# Pin28_Schematic.net
KiCad netlist of a schematic drawn in Altium Designer
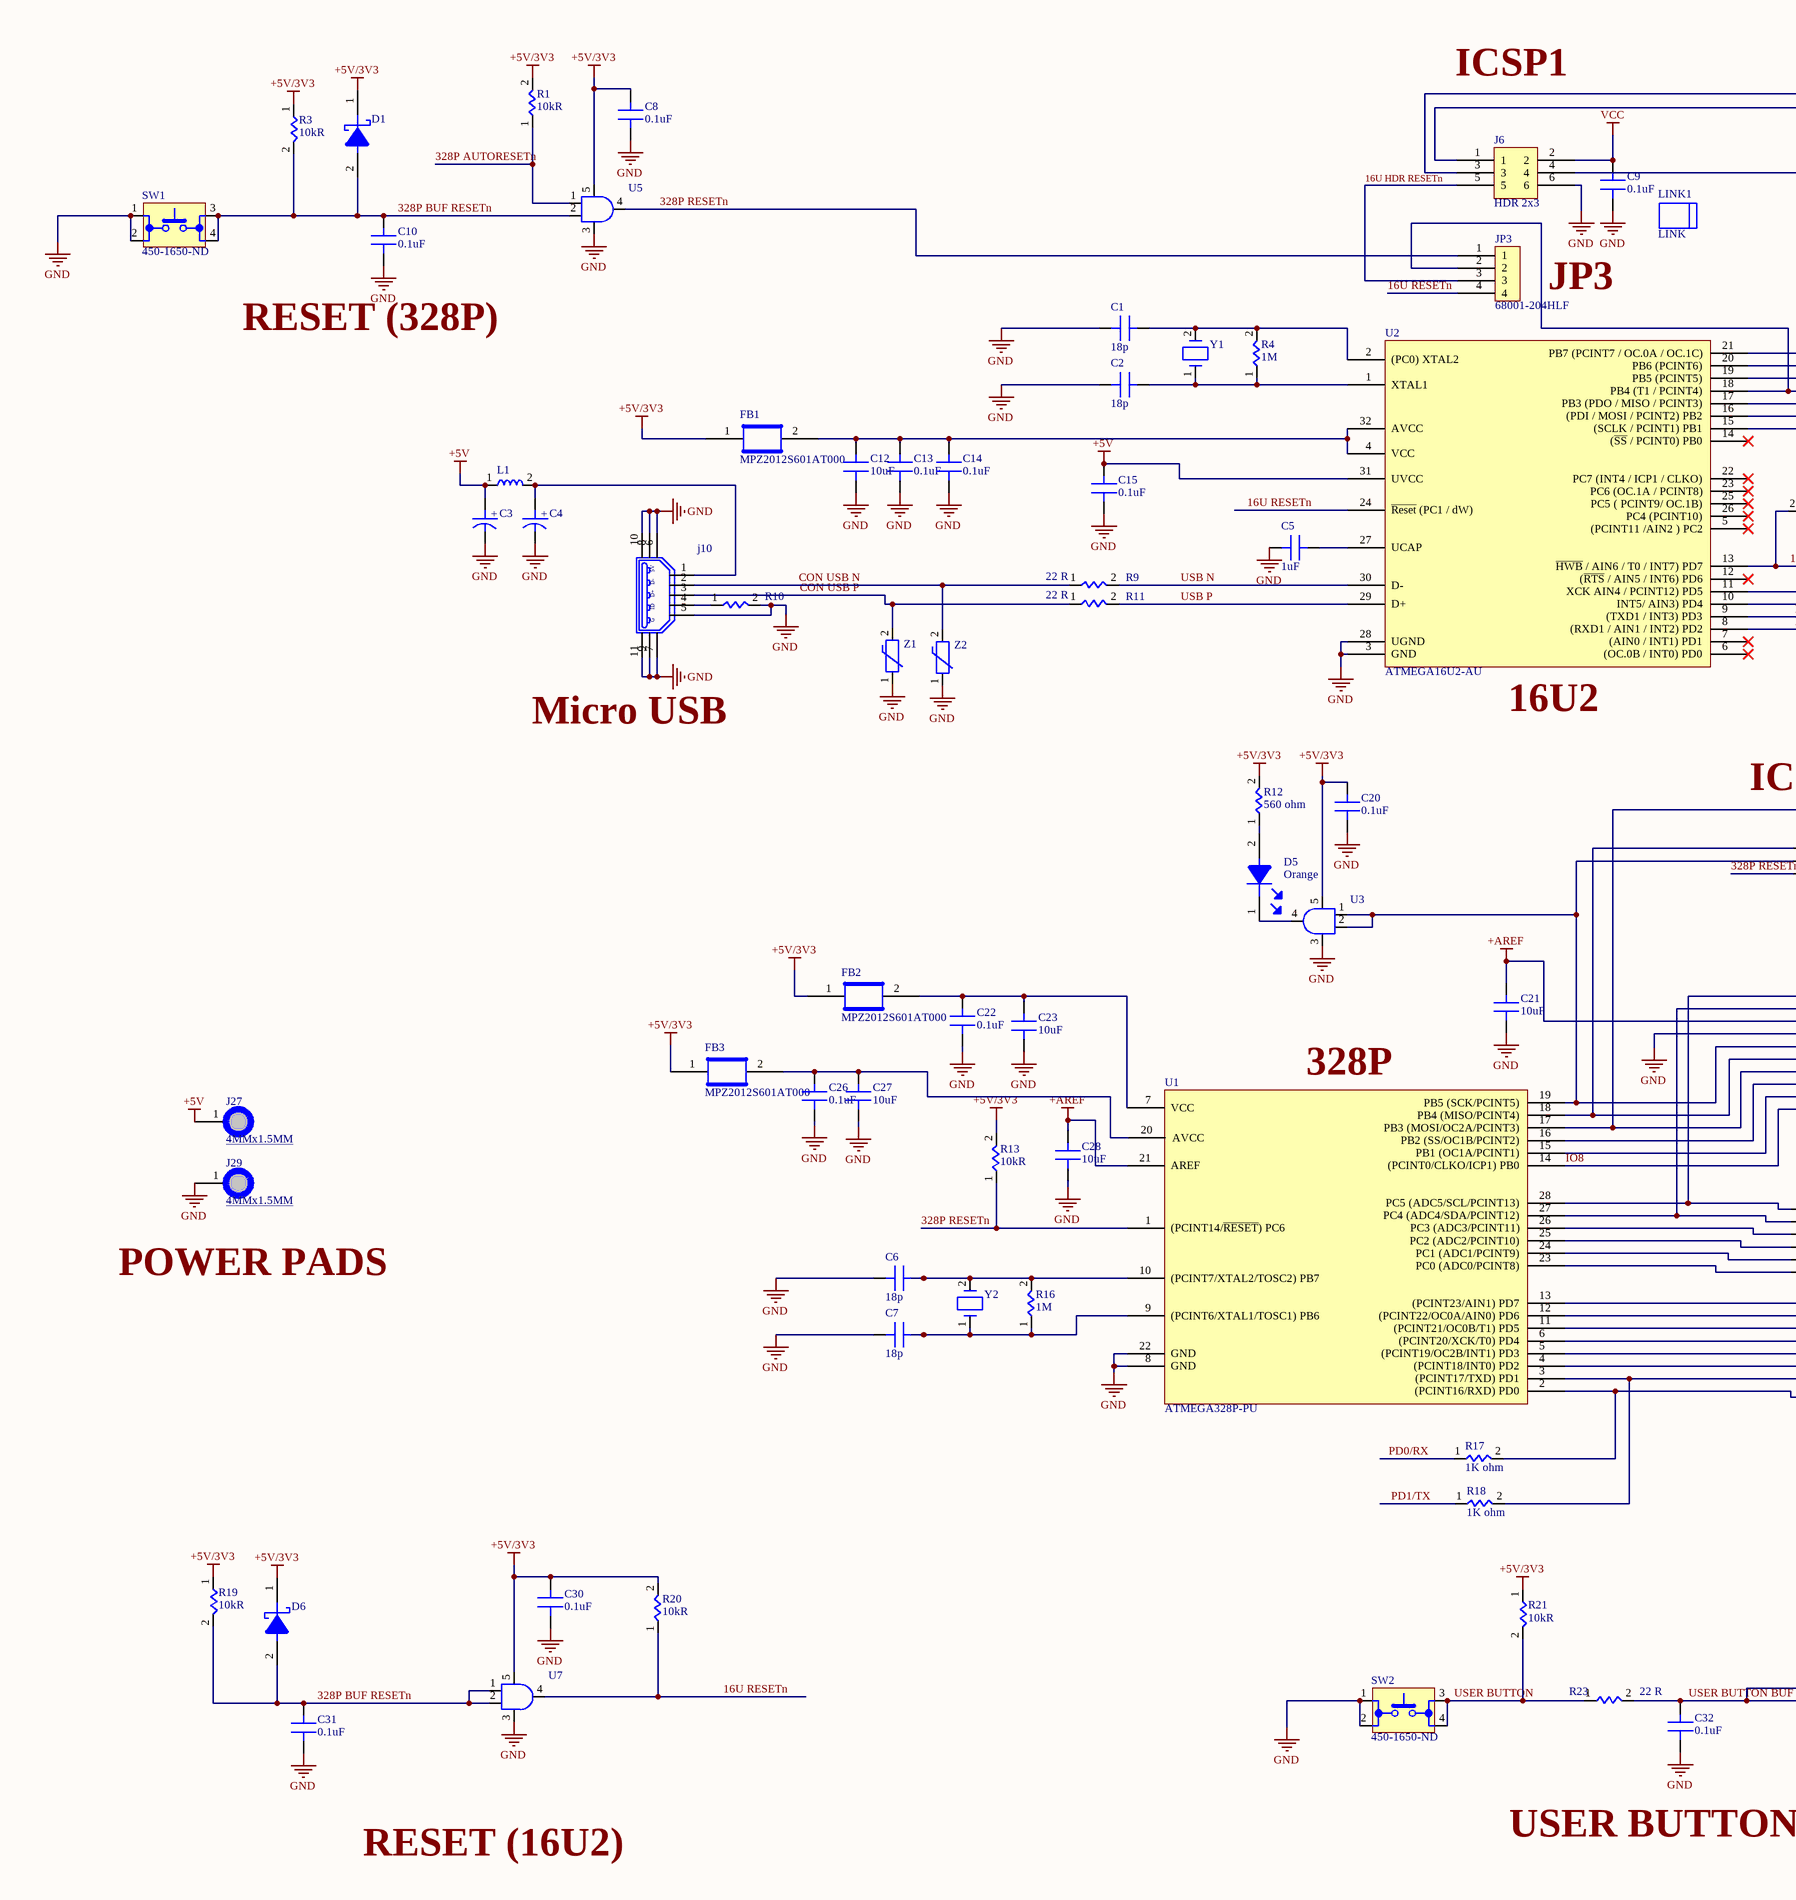
[diagram p0: Pin28_Schematic.SchDoc, left]
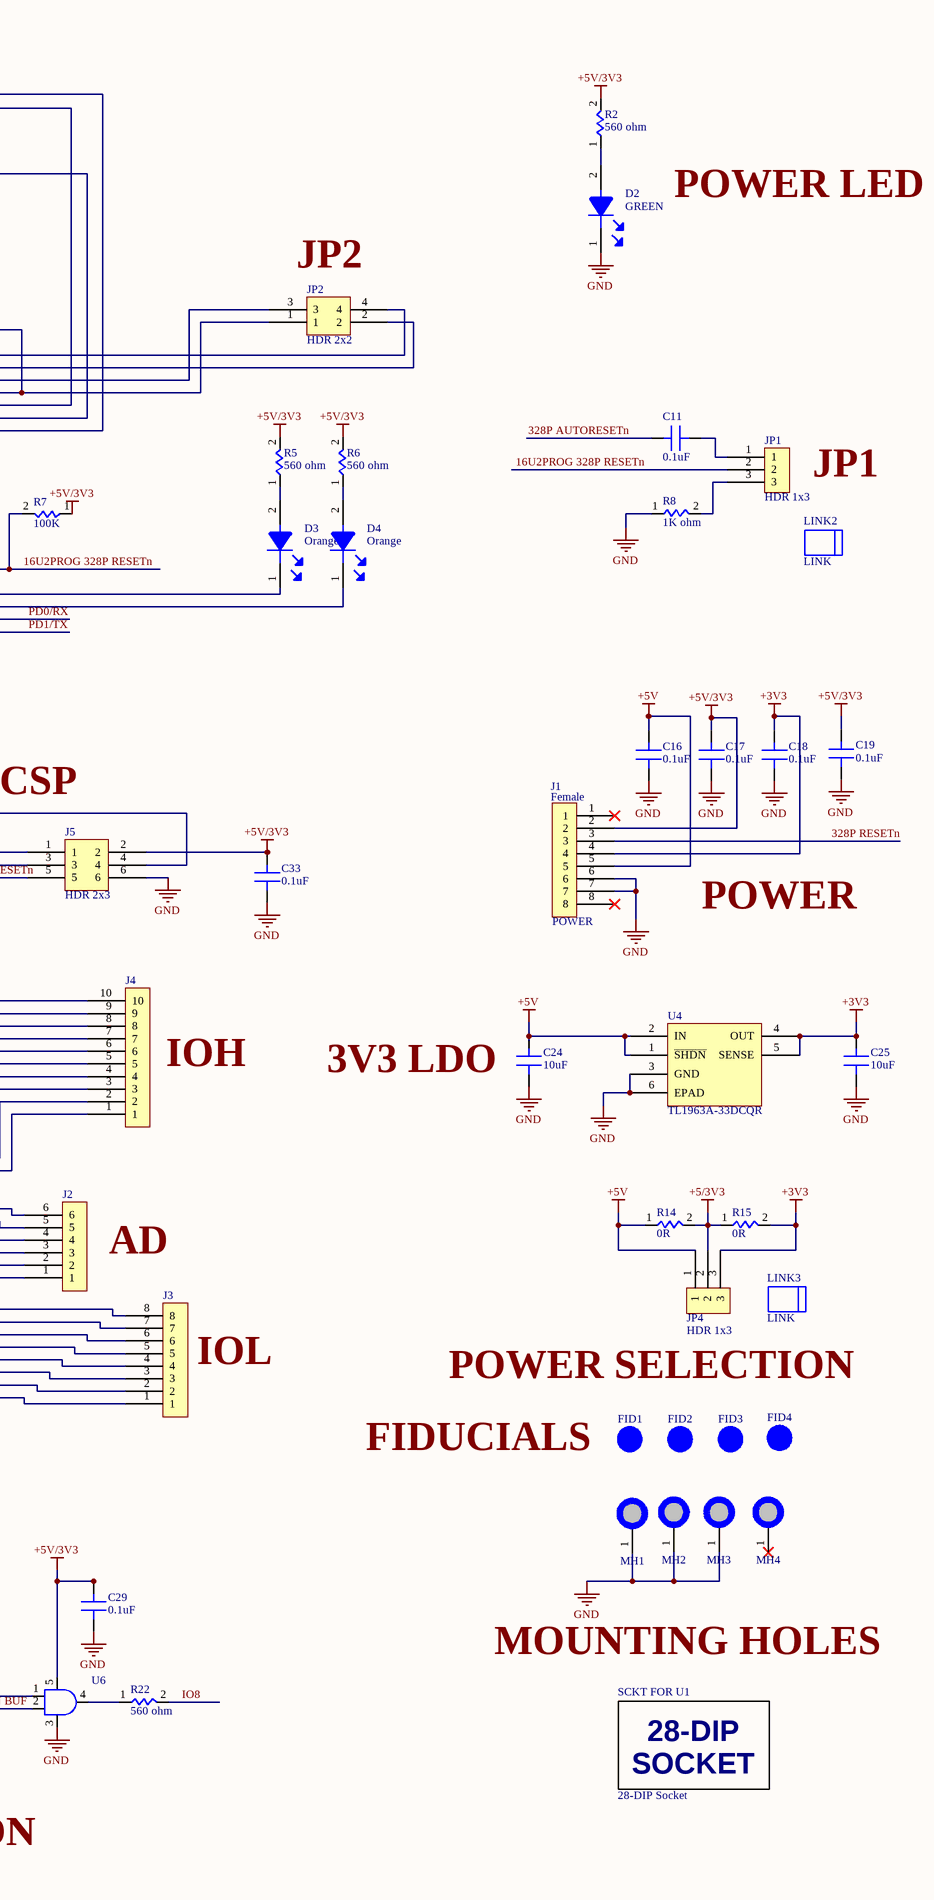
[diagram p1: Pin28_Schematic.SchDoc, right]

(export (version "E")
  (design (tool "Eeschema 10.0.6"))
  (components
    (comp (ref "C1")
      (value "18p")
      (footprint "C0805 0.1 UF Footprint")
      (description "CAP CER 18PF 50V C0G/NP0 0805")
      (fields
        (field (name "MANUFACTURER") "KEMET")
        (field (name "MANUFACTURER PART NUMBER") "C0805C180J5GACTU")
      )
      (libsource (lib "Pin28_Schematic_Library") (part "C0805C180J5GACTU"))
    )
    (comp (ref "C2")
      (value "18p")
      (footprint "C0805 0.1 UF Footprint")
      (description "CAP CER 18PF 50V C0G/NP0 0805")
      (fields
        (field (name "MANUFACTURER") "KEMET")
        (field (name "MANUFACTURER PART NUMBER") "C0805C180J5GACTU")
      )
      (libsource (lib "Pin28_Schematic_Library") (part "C0805C180J5GACTU"))
    )
    (comp (ref "C3")
      (value "EEE-1AA101WR")
      (footprint "C_ALU_C_SIZE")
      (description "Cap Aluminum 100uF 10V 20% (5 X 5.4mm) SMD 50mA 1000 hr 85°C T/R")
      (fields (field (name "MANUFACTURER") "Panasonic") (field (name "TOLERANCE") "20%"))
      (libsource (lib "Pin28_Schematic_Library") (part "EEE-1AA101WR"))
    )
    (comp (ref "C4")
      (value "EEE-1AA101WR")
      (footprint "C_ALU_C_SIZE")
      (description "Cap Aluminum 100uF 10V 20% (5 X 5.4mm) SMD 50mA 1000 hr 85°C T/R")
      (fields (field (name "MANUFACTURER") "Panasonic") (field (name "TOLERANCE") "20%"))
      (libsource (lib "Pin28_Schematic_Library") (part "EEE-1AA101WR"))
    )
    (comp (ref "C5")
      (value "1uF")
      (footprint "C0805 10 uF Footprint")
      (fields
        (field (name "MANUFACTURER") "TDK")
        (field (name "MANUFACTURER PART NUMBER") "C2012X5R1E105K125AA")
        (field (name "TOLERANCE") "10%")
      )
      (libsource (lib "Pin28_Schematic_Library") (part "C2012X5R1E105K125AA"))
    )
    (comp (ref "C6")
      (value "18p")
      (footprint "C0805 0.1 UF Footprint")
      (description "CAP CER 18PF 50V C0G/NP0 0805")
      (fields
        (field (name "MANUFACTURER") "KEMET")
        (field (name "MANUFACTURER PART NUMBER") "C0805C180J5GACTU")
      )
      (libsource (lib "Pin28_Schematic_Library") (part "C0805C180J5GACTU"))
    )
    (comp (ref "C7")
      (value "18p")
      (footprint "C0805 0.1 UF Footprint")
      (description "CAP CER 18PF 50V C0G/NP0 0805")
      (fields
        (field (name "MANUFACTURER") "KEMET")
        (field (name "MANUFACTURER PART NUMBER") "C0805C180J5GACTU")
      )
      (libsource (lib "Pin28_Schematic_Library") (part "C0805C180J5GACTU"))
    )
    (comp (ref "C8")
      (value "0.1uF")
      (footprint "C0805 0.1 UF Footprint")
      (fields
        (field (name "TOLERANCE") "10%")
        (field (name "VOLTAGE") "50V")
        (field (name "MANUFACTURER") "TDK")
      )
      (libsource (lib "Pin28_Schematic_Library") (part "C2012X7R1H104K085AA"))
    )
    (comp (ref "C9")
      (value "0.1uF")
      (footprint "C0805 0.1 UF Footprint")
      (fields
        (field (name "TOLERANCE") "10%")
        (field (name "VOLTAGE") "50V")
        (field (name "MANUFACTURER") "TDK")
      )
      (libsource (lib "Pin28_Schematic_Library") (part "C2012X7R1H104K085AA"))
    )
    (comp (ref "C10")
      (value "0.1uF")
      (footprint "C0805 0.1 UF Footprint")
      (fields
        (field (name "TOLERANCE") "10%")
        (field (name "VOLTAGE") "50V")
        (field (name "MANUFACTURER") "TDK")
      )
      (libsource (lib "Pin28_Schematic_Library") (part "C2012X7R1H104K085AA"))
    )
    (comp (ref "C11")
      (value "0.1uF")
      (footprint "C0805 0.1 UF Footprint")
      (fields
        (field (name "TOLERANCE") "10%")
        (field (name "VOLTAGE") "50V")
        (field (name "MANUFACTURER") "TDK")
      )
      (libsource (lib "Pin28_Schematic_Library") (part "C2012X7R1H104K085AA"))
    )
    (comp (ref "C12")
      (value "10uF")
      (footprint "C0805 10 uF Footprint")
      (fields
        (field (name "MANUFACTURER") "TDK")
        (field (name "TOLERANCE") "20%")
        (field (name "MANUFACTURER PART NUMBER") "C2012X5R1C106M125AC")
      )
      (libsource (lib "Pin28_Schematic_Library") (part "C2012X5R1C106M125AC"))
    )
    (comp (ref "C13")
      (value "0.1uF")
      (footprint "C0805 0.1 UF Footprint")
      (fields
        (field (name "TOLERANCE") "10%")
        (field (name "VOLTAGE") "50V")
        (field (name "MANUFACTURER") "TDK")
      )
      (libsource (lib "Pin28_Schematic_Library") (part "C2012X7R1H104K085AA"))
    )
    (comp (ref "C14")
      (value "0.1uF")
      (footprint "C0805 0.1 UF Footprint")
      (fields
        (field (name "TOLERANCE") "10%")
        (field (name "VOLTAGE") "50V")
        (field (name "MANUFACTURER") "TDK")
      )
      (libsource (lib "Pin28_Schematic_Library") (part "C2012X7R1H104K085AA"))
    )
    (comp (ref "C15")
      (value "0.1uF")
      (footprint "C0805 0.1 UF Footprint")
      (fields
        (field (name "TOLERANCE") "10%")
        (field (name "VOLTAGE") "50V")
        (field (name "MANUFACTURER") "TDK")
      )
      (libsource (lib "Pin28_Schematic_Library") (part "C2012X7R1H104K085AA"))
    )
    (comp (ref "C16")
      (value "0.1uF")
      (footprint "C0805 0.1 UF Footprint")
      (fields
        (field (name "TOLERANCE") "10%")
        (field (name "VOLTAGE") "50V")
        (field (name "MANUFACTURER") "TDK")
      )
      (libsource (lib "Pin28_Schematic_Library") (part "C2012X7R1H104K085AA"))
    )
    (comp (ref "C17")
      (value "0.1uF")
      (footprint "C0805 0.1 UF Footprint")
      (fields
        (field (name "TOLERANCE") "10%")
        (field (name "VOLTAGE") "50V")
        (field (name "MANUFACTURER") "TDK")
      )
      (libsource (lib "Pin28_Schematic_Library") (part "C2012X7R1H104K085AA"))
    )
    (comp (ref "C18")
      (value "0.1uF")
      (footprint "C0805 0.1 UF Footprint")
      (fields
        (field (name "TOLERANCE") "10%")
        (field (name "VOLTAGE") "50V")
        (field (name "MANUFACTURER") "TDK")
      )
      (libsource (lib "Pin28_Schematic_Library") (part "C2012X7R1H104K085AA"))
    )
    (comp (ref "C19")
      (value "0.1uF")
      (footprint "C0805 0.1 UF Footprint")
      (fields
        (field (name "TOLERANCE") "10%")
        (field (name "VOLTAGE") "50V")
        (field (name "MANUFACTURER") "TDK")
      )
      (libsource (lib "Pin28_Schematic_Library") (part "C2012X7R1H104K085AA"))
    )
    (comp (ref "C20")
      (value "0.1uF")
      (footprint "C0805 0.1 UF Footprint")
      (fields
        (field (name "TOLERANCE") "10%")
        (field (name "VOLTAGE") "50V")
        (field (name "MANUFACTURER") "TDK")
      )
      (libsource (lib "Pin28_Schematic_Library") (part "C2012X7R1H104K085AA"))
    )
    (comp (ref "C21")
      (value "10uF")
      (footprint "C0805 10 uF Footprint")
      (fields
        (field (name "MANUFACTURER") "TDK")
        (field (name "TOLERANCE") "20%")
        (field (name "MANUFACTURER PART NUMBER") "C2012X5R1C106M125AC")
      )
      (libsource (lib "Pin28_Schematic_Library") (part "C2012X5R1C106M125AC"))
    )
    (comp (ref "C22")
      (value "0.1uF")
      (footprint "C0805 0.1 UF Footprint")
      (fields
        (field (name "TOLERANCE") "10%")
        (field (name "VOLTAGE") "50V")
        (field (name "MANUFACTURER") "TDK")
      )
      (libsource (lib "Pin28_Schematic_Library") (part "C2012X7R1H104K085AA"))
    )
    (comp (ref "C23")
      (value "10uF")
      (footprint "C0805 10 uF Footprint")
      (fields
        (field (name "MANUFACTURER") "TDK")
        (field (name "TOLERANCE") "20%")
        (field (name "MANUFACTURER PART NUMBER") "C2012X5R1C106M125AC")
      )
      (libsource (lib "Pin28_Schematic_Library") (part "C2012X5R1C106M125AC"))
    )
    (comp (ref "C24")
      (value "10uF")
      (footprint "C0805 10 uF Footprint")
      (fields
        (field (name "MANUFACTURER") "TDK")
        (field (name "TOLERANCE") "20%")
        (field (name "MANUFACTURER PART NUMBER") "C2012X5R1C106M125AC")
      )
      (libsource (lib "Pin28_Schematic_Library") (part "C2012X5R1C106M125AC"))
    )
    (comp (ref "C25")
      (value "10uF")
      (footprint "C0805 10 uF Footprint")
      (fields
        (field (name "MANUFACTURER") "TDK")
        (field (name "TOLERANCE") "20%")
        (field (name "MANUFACTURER PART NUMBER") "C2012X5R1C106M125AC")
      )
      (libsource (lib "Pin28_Schematic_Library") (part "C2012X5R1C106M125AC"))
    )
    (comp (ref "C26")
      (value "0.1uF")
      (footprint "C0805 0.1 UF Footprint")
      (fields
        (field (name "TOLERANCE") "10%")
        (field (name "VOLTAGE") "50V")
        (field (name "MANUFACTURER") "TDK")
      )
      (libsource (lib "Pin28_Schematic_Library") (part "C2012X7R1H104K085AA"))
    )
    (comp (ref "C27")
      (value "10uF")
      (footprint "C0805 10 uF Footprint")
      (fields
        (field (name "MANUFACTURER") "TDK")
        (field (name "TOLERANCE") "20%")
        (field (name "MANUFACTURER PART NUMBER") "C2012X5R1C106M125AC")
      )
      (libsource (lib "Pin28_Schematic_Library") (part "C2012X5R1C106M125AC"))
    )
    (comp (ref "C28")
      (value "10uF")
      (footprint "C0805 10 uF Footprint")
      (fields
        (field (name "MANUFACTURER") "TDK")
        (field (name "TOLERANCE") "20%")
        (field (name "MANUFACTURER PART NUMBER") "C2012X5R1C106M125AC")
      )
      (libsource (lib "Pin28_Schematic_Library") (part "C2012X5R1C106M125AC"))
    )
    (comp (ref "C29")
      (value "0.1uF")
      (footprint "C0805 0.1 UF Footprint")
      (fields
        (field (name "TOLERANCE") "10%")
        (field (name "VOLTAGE") "50V")
        (field (name "MANUFACTURER") "TDK")
      )
      (libsource (lib "Pin28_Schematic_Library") (part "C2012X7R1H104K085AA"))
    )
    (comp (ref "C30")
      (value "0.1uF")
      (footprint "C0805 0.1 UF Footprint")
      (fields
        (field (name "TOLERANCE") "10%")
        (field (name "VOLTAGE") "50V")
        (field (name "MANUFACTURER") "TDK")
      )
      (libsource (lib "Pin28_Schematic_Library") (part "C2012X7R1H104K085AA"))
    )
    (comp (ref "C31")
      (value "0.1uF")
      (footprint "C0805 0.1 UF Footprint")
      (fields
        (field (name "TOLERANCE") "10%")
        (field (name "VOLTAGE") "50V")
        (field (name "MANUFACTURER") "TDK")
      )
      (libsource (lib "Pin28_Schematic_Library") (part "C2012X7R1H104K085AA"))
    )
    (comp (ref "C32")
      (value "0.1uF")
      (footprint "C0805 0.1 UF Footprint")
      (fields
        (field (name "TOLERANCE") "10%")
        (field (name "VOLTAGE") "50V")
        (field (name "MANUFACTURER") "TDK")
      )
      (libsource (lib "Pin28_Schematic_Library") (part "C2012X7R1H104K085AA"))
    )
    (comp (ref "C33")
      (value "0.1uF")
      (footprint "C0805 0.1 UF Footprint")
      (fields
        (field (name "TOLERANCE") "10%")
        (field (name "VOLTAGE") "50V")
        (field (name "MANUFACTURER") "TDK")
      )
      (libsource (lib "Pin28_Schematic_Library") (part "C2012X7R1H104K085AA"))
    )
    (comp (ref "D1")
      (value "BAT54HT1G")
      (footprint "SOD323")
      (description "Small Signal Schottky Diode, Single, 30 V, 200 mA, 800 mV, 600 mA, 150 C ;RoHS Compliant: Yes")
      (fields (field (name "MANUFACTURER") "ON Semiconductor / Fairchild"))
      (libsource (lib "Pin28_Schematic_Library") (part "BAT54HT1G"))
    )
    (comp (ref "D2")
      (value "GREEN")
      (footprint "LED_0603")
      (description "LED Uni-Color Green 572nm 2-Pin Chip 0603(1608Metric) T/R")
      (fields
        (field (name "MANUFACTURER") "Osram Opto")
        (field (name "MANUFACTURER PART NUMBER") "LGL29K-G2J1-24-Z")
      )
      (libsource (lib "Pin28_Schematic_Library") (part "LGL29K-G2J1-24-Z"))
    )
    (comp (ref "D3")
      (value "Orange")
      (footprint "LED_0603")
      (description "OSRAM - LO L29K-H2K1-24-Z - SMARTLED 0603 ORANGE")
      (fields
        (field (name "MANUFACTURER") "Osram Opto")
        (field (name "MANUFACTURER PART NUMBER") "LOL29K-H2K1-24-Z")
      )
      (libsource (lib "Pin28_Schematic_Library") (part "LOL29K-H2K1-24-Z"))
    )
    (comp (ref "D4")
      (value "Orange")
      (footprint "LED_0603")
      (description "OSRAM - LO L29K-H2K1-24-Z - SMARTLED 0603 ORANGE")
      (fields
        (field (name "MANUFACTURER") "Osram Opto")
        (field (name "MANUFACTURER PART NUMBER") "LOL29K-H2K1-24-Z")
      )
      (libsource (lib "Pin28_Schematic_Library") (part "LOL29K-H2K1-24-Z"))
    )
    (comp (ref "D5")
      (value "Orange")
      (footprint "LED_0603")
      (description "OSRAM - LO L29K-H2K1-24-Z - SMARTLED 0603 ORANGE")
      (fields
        (field (name "MANUFACTURER") "Osram Opto")
        (field (name "MANUFACTURER PART NUMBER") "LOL29K-H2K1-24-Z")
      )
      (libsource (lib "Pin28_Schematic_Library") (part "LOL29K-H2K1-24-Z"))
    )
    (comp (ref "D6")
      (value "BAT54HT1G")
      (footprint "SOD323")
      (description "Small Signal Schottky Diode, Single, 30 V, 200 mA, 800 mV, 600 mA, 150 C ;RoHS Compliant: Yes")
      (fields (field (name "MANUFACTURER") "ON Semiconductor / Fairchild"))
      (libsource (lib "Pin28_Schematic_Library") (part "BAT54HT1G"))
    )
    (comp (ref "FB1")
      (value "MPZ2012S601AT000")
      (footprint "C0805 0.1 UF Footprint")
      (description "FERRITE BEAD 600 OHM 0805 1LN")
      (fields (field (name "MANUFACTURER") "TDK"))
      (libsource (lib "Pin28_Schematic_Library") (part "MPZ2012S601AT000"))
    )
    (comp (ref "FB2")
      (value "MPZ2012S601AT000")
      (footprint "C0805 0.1 UF Footprint")
      (description "FERRITE BEAD 600 OHM 0805 1LN")
      (fields (field (name "MANUFACTURER") "TDK"))
      (libsource (lib "Pin28_Schematic_Library") (part "MPZ2012S601AT000"))
    )
    (comp (ref "FB3")
      (value "MPZ2012S601AT000")
      (footprint "C0805 0.1 UF Footprint")
      (description "FERRITE BEAD 600 OHM 0805 1LN")
      (fields (field (name "MANUFACTURER") "TDK"))
      (libsource (lib "Pin28_Schematic_Library") (part "MPZ2012S601AT000"))
    )
    (comp (ref "FID1")
      (value "FID_1MM")
      (footprint "FID_40x120")
      (description "Fiducial 40 mil Diameter, 123 mil Mask")
      (libsource (lib "Pin28_Schematic_Library") (part "FID_1MM"))
    )
    (comp (ref "FID2")
      (value "FID_1MM")
      (footprint "FID_40x120")
      (description "Fiducial 40 mil Diameter, 123 mil Mask")
      (libsource (lib "Pin28_Schematic_Library") (part "FID_1MM"))
    )
    (comp (ref "FID3")
      (value "FID_1MM")
      (footprint "FID_40x120")
      (description "Fiducial 40 mil Diameter, 123 mil Mask")
      (libsource (lib "Pin28_Schematic_Library") (part "FID_1MM"))
    )
    (comp (ref "FID4")
      (value "FID_1MM")
      (footprint "FID_40x120")
      (description "Fiducial 40 mil Diameter, 123 mil Mask")
      (libsource (lib "Pin28_Schematic_Library") (part "FID_1MM"))
    )
    (comp (ref "J1")
      (value "POWER")
      (footprint "Header Female 8 2.54 mm")
      (description "08 contacts 2.54mm (0.1\") Pitch SIL Vertical PC Tail Socket Assembly, selective gold + tin")
      (fields
        (field (name "MANUFACTURER") "Harwin")
        (field (name "CONTACT GENDER") "Female")
        (field (name "MANUFACTURER PART NUMBER") "M20-7820842")
      )
      (libsource (lib "Pin28_Schematic_Library") (part "M20-7820842"))
    )
    (comp (ref "J2")
      (value "M20-7820646")
      (footprint "Header Female 6 2.54 mm")
      (description "06-WAY SIL VERT SOCKET L/FREE")
      (fields (field (name "MANUFACTURER") "Harwin"))
      (libsource (lib "Pin28_Schematic_Library") (part "M20-7820646"))
    )
    (comp (ref "J3")
      (value "08 contacts 2.54mm (0.1\") Pitch SIL Vertical PC Tail Socket Assembly, selective gold + tin")
      (footprint "Header Female 8 2.54 mm")
      (fields (field (name "MANUFACTURER") "Harwin") (field (name "MANUFACTURER PART NUMBER") "M20-7820842"))
      (libsource (lib "") (part "M20-7820842_1"))
    )
    (comp (ref "J4")
      (value "10 contacts - M20-7821046 - Board-To-Board Connector, M20 Series, Through Hole, Receptacle, 10, 2.54 mm, Tin Plated Contacts")
      (footprint "Header Female 10 2.54 mm")
      (fields (field (name "MANUFACTURER") "Harwin") (field (name "MANUFACTURER PART NUMBER") "M20-7821046"))
      (libsource (lib "Pin28_Schematic_Library") (part "M20-7821046"))
    )
    (comp (ref "J5")
      (value "HDR 2x3")
      (footprint "HDR 2x3 2.54mm")
      (description "CONN HEADER 6POS .100 STR 30AU")
      (fields
        (field (name "MANUFACTURER") "Amphenol FCI")
        (field (name "MANUFACTURER PART NUMBER") "67997-106HLF")
      )
      (libsource (lib "Pin28_Schematic_Library") (part "67997-106HLF"))
    )
    (comp (ref "J6")
      (value "HDR 2x3")
      (footprint "HDR 2x3 2.54mm")
      (description "CONN HEADER 6POS .100 STR 30AU")
      (fields
        (field (name "MANUFACTURER") "Amphenol FCI")
        (field (name "MANUFACTURER PART NUMBER") "67997-106HLF")
      )
      (libsource (lib "Pin28_Schematic_Library") (part "67997-106HLF"))
    )
    (comp (ref "j10")
      (value "10118193-0001LF")
      (footprint "10118193")
      (description "CONN USB MICRO B RECPT SMT R/A")
      (fields (field (name "MANUFACTURER") "Amphenol FCI"))
      (libsource (lib "Pin28_Schematic_Library") (part "10118193-0001LF"))
    )
    (comp (ref "J27")
      (value "4MMx1.5MM")
      (footprint "PAD_4MMx1.5MM")
      (libsource (lib "Pin28_Schematic_Library") (part "PAD_with_hole_4MM_1.5MM"))
    )
    (comp (ref "J29")
      (value "4MMx1.5MM")
      (footprint "PAD_4MMx1.5MM")
      (libsource (lib "Pin28_Schematic_Library") (part "PAD_with_hole_4MM_1.5MM"))
    )
    (comp (ref "JP1")
      (value "HDR 1x3")
      (footprint "Header Male HDR 1x3 2.54 mm")
      (description "Conn Unshrouded Header HDR 3 POS 2.54mm Solder ST Thru-Hole Bulk")
      (fields
        (field (name "MANUFACTURER") "Amphenol FCI")
        (field (name "MANUFACTURER PART NUMBER") "68000-103HLF")
      )
      (libsource (lib "Pin28_Schematic_Library") (part "68000-103HLF"))
    )
    (comp (ref "JP2")
      (value "HDR 2x2")
      (footprint "HDR 2x2 2.54mm")
      (description "CONN HEADER VERT 4POS 2.54MM")
      (fields
        (field (name "MANUFACTURER") "Amphenol FCI")
        (field (name "MANUFACTURER PART NUMBER") "68602-204HLF")
      )
      (libsource (lib "Pin28_Schematic_Library") (part "68602-204HLF"))
    )
    (comp (ref "JP3")
      (value "68001-204HLF")
      (footprint "Header MALE HDR 1x4 2.54 mm")
      (description "CONN HEADER VERT 4POS 2.54MM")
      (fields (field (name "MANUFACTURER") "Amphenol FCI"))
      (libsource (lib "Pin28_Schematic_Library") (part "68001-204HLF"))
    )
    (comp (ref "JP4")
      (value "HDR 1x3")
      (footprint "Header Male HDR 1x3 2.54 mm")
      (description "Conn Unshrouded Header HDR 3 POS 2.54mm Solder ST Thru-Hole Bulk")
      (fields
        (field (name "MANUFACTURER") "Amphenol FCI")
        (field (name "MANUFACTURER PART NUMBER") "68000-103HLF")
      )
      (libsource (lib "") (part "68000-103HLF_1"))
    )
    (comp (ref "L1")
      (value "L1210R2R2MDWIT")
      (footprint "C1210_IND")
      (description "FIXED IND 2.2UH 2A 80 MOHM SMD")
      (fields (field (name "MANUFACTURER") "KEMET") (field (name "TOLERANCE") "20%"))
      (libsource (lib "Pin28_Schematic_Library") (part "L1210R2R2MDWIT"))
    )
    (comp (ref "LINK1")
      (value "LINK")
      (description "CONN JUMPER SHORTING .100\" GOLD")
      (fields
        (field (name "MANUFACTURER") "Sullins")
        (field (name "MANUFACTURER PART NUMBER") "QPC02SXGN-RC")
      )
      (libsource (lib "Pin28_Schematic_Library") (part "QPC02SXGN-RC"))
    )
    (comp (ref "LINK2")
      (value "LINK")
      (description "CONN JUMPER SHORTING .100\" GOLD")
      (fields
        (field (name "MANUFACTURER") "Sullins")
        (field (name "MANUFACTURER PART NUMBER") "QPC02SXGN-RC")
      )
      (libsource (lib "Pin28_Schematic_Library") (part "QPC02SXGN-RC"))
    )
    (comp (ref "LINK3")
      (value "LINK")
      (description "CONN JUMPER SHORTING .100\" GOLD")
      (fields
        (field (name "MANUFACTURER") "Sullins")
        (field (name "MANUFACTURER PART NUMBER") "QPC02SXGN-RC")
      )
      (libsource (lib "Pin28_Schematic_Library") (part "QPC02SXGN-RC"))
    )
    (comp (ref "MH1")
      (value "MH7.4MMc_3.2MMD")
      (footprint "MH7.4MMD_3.2MMD")
      (description "Mounting Hole 7.4MM Diameter, 3.2mm Drill")
      (libsource (lib "Pin28_Schematic_Library") (part "MH_7.4MMC_3.2MMD"))
    )
    (comp (ref "MH2")
      (value "MH7.4MMc_3.2MMD")
      (footprint "MH7.4MMD_3.2MMD")
      (description "Mounting Hole 7.4MM Diameter, 3.2mm Drill")
      (libsource (lib "Pin28_Schematic_Library") (part "MH_7.4MMC_3.2MMD"))
    )
    (comp (ref "MH3")
      (value "MH7.4MMc_3.2MMD")
      (footprint "MH7.4MMD_3.2MMD")
      (description "Mounting Hole 7.4MM Diameter, 3.2mm Drill")
      (libsource (lib "Pin28_Schematic_Library") (part "MH_7.4MMC_3.2MMD"))
    )
    (comp (ref "MH4")
      (value "MH_7.4MMNC_3.2MMD")
      (footprint "MH_7.4MMND_3.2MMD_NON_COPPER")
      (description "Hole_7.4_Diameter(Non Copper), 3.2 Drill")
      (libsource (lib "Pin28_Schematic_Library") (part "MH7.4MMNC_3.2MMC"))
    )
    (comp (ref "R1")
      (value "RC0805FR-0710KL")
      (footprint "R0805 1K")
      (description "RES SMD 10K OHM 1% 1/8W 0805")
      (fields
        (field (name "MANUFACTURER") "Yageo")
        (field (name "TOLERANCE") "1%")
        (field (name "RESISTANCE") "10kR")
      )
      (libsource (lib "Pin28_Schematic_Library") (part "RC0805FR-0710KL"))
    )
    (comp (ref "R2")
      (value "560 ohm")
      (footprint "R0805 1K")
      (description "Surface Mount Thick Film Resistor, RC Series, 560 ohm, 125 mW, - 1%, 150 V, 0805 [2012 Metric]")
      (fields
        (field (name "MANUFACTURER") "Yageo")
        (field (name "MANUFACTURER PART NUMBER") "RC0805FR-07560RL")
      )
      (libsource (lib "Pin28_Schematic_Library") (part "RC0805FR-07560RL"))
    )
    (comp (ref "R3")
      (value "RC0805FR-0710KL")
      (footprint "R0805 1K")
      (description "RES SMD 10K OHM 1% 1/8W 0805")
      (fields
        (field (name "MANUFACTURER") "Yageo")
        (field (name "TOLERANCE") "1%")
        (field (name "RESISTANCE") "10kR")
      )
      (libsource (lib "Pin28_Schematic_Library") (part "RC0805FR-0710KL"))
    )
    (comp (ref "R4")
      (value "1M")
      (footprint "R0805 1M")
      (description "1M Ohm Res Thick Film 0805 1% 0.125W(1/8W) ±100ppm/C Epoxy SMD T/R")
      (fields (field (name "MANUFACTURER") "Yageo Phycomp") (field (name "TOLERANCE") "1%"))
      (libsource (lib "Pin28_Schematic_Library") (part "RC0805FR-071ML"))
    )
    (comp (ref "R5")
      (value "560 ohm")
      (footprint "R0805 1K")
      (description "Surface Mount Thick Film Resistor, RC Series, 560 ohm, 125 mW, - 1%, 150 V, 0805 [2012 Metric]")
      (fields
        (field (name "MANUFACTURER") "Yageo")
        (field (name "MANUFACTURER PART NUMBER") "RC0805FR-07560RL")
      )
      (libsource (lib "Pin28_Schematic_Library") (part "RC0805FR-07560RL"))
    )
    (comp (ref "R6")
      (value "560 ohm")
      (footprint "R0805 1K")
      (description "Surface Mount Thick Film Resistor, RC Series, 560 ohm, 125 mW, - 1%, 150 V, 0805 [2012 Metric]")
      (fields
        (field (name "MANUFACTURER") "Yageo")
        (field (name "MANUFACTURER PART NUMBER") "RC0805FR-07560RL")
      )
      (libsource (lib "Pin28_Schematic_Library") (part "RC0805FR-07560RL"))
    )
    (comp (ref "R7")
      (value "100K")
      (footprint "R0805 1K")
      (description "YAGEO         RC0805FR-07100KL            RES, THICK FILM, 100K, 1%, 0.125W, 0805, REEL")
      (fields
        (field (name "MANUFACTURER") "Yageo")
        (field (name "MANUFACTURER PART NUMBER") "RC0805FR-07100KL")
      )
      (libsource (lib "Pin28_Schematic_Library") (part "RC0805FR-07100KL"))
    )
    (comp (ref "R8")
      (value "1K ohm")
      (footprint "R0805 1M")
      (fields
        (field (name "MANUFACTURER") "Yageo")
        (field (name "MANUFACTURER PART NUMBER") "RC0805FR-071KL")
        (field (name "TOLERANCE") "1%")
      )
      (libsource (lib "Pin28_Schematic_Library") (part "RC0805FR-071KL"))
    )
    (comp (ref "R9")
      (value "22 R")
      (footprint "R0805 1K")
      (description "RES SMD 22 OHM 1% 1/8W 0805")
      (fields
        (field (name "MANUFACTURER") "Yageo")
        (field (name "MANUFACTURER PART NUMBER") "AC0805FR-0722RL")
      )
      (libsource (lib "Pin28_Schematic_Library") (part "AC0805FR-0722RL"))
    )
    (comp (ref "R10")
      (value "0R/RC0805JR-070RL")
      (footprint "R0805 1K")
      (description "Surface Mount Thick Film Resistor, RC Series, 125 mW, - 5%, 150 V, 0805 [2012 Metric]")
      (fields
        (field (name "MANUFACTURER") "Yageo")
        (field (name "MANUFACTURER PART NUMBER") "RC0805JR-070RL")
      )
      (libsource (lib "Pin28_Schematic_Library") (part "RC0805JR-070RL"))
    )
    (comp (ref "R11")
      (value "22 R")
      (footprint "R0805 1K")
      (description "RES SMD 22 OHM 1% 1/8W 0805")
      (fields
        (field (name "MANUFACTURER") "Yageo")
        (field (name "MANUFACTURER PART NUMBER") "AC0805FR-0722RL")
      )
      (libsource (lib "Pin28_Schematic_Library") (part "AC0805FR-0722RL"))
    )
    (comp (ref "R12")
      (value "560 ohm")
      (footprint "R0805 1K")
      (description "Surface Mount Thick Film Resistor, RC Series, 560 ohm, 125 mW, - 1%, 150 V, 0805 [2012 Metric]")
      (fields
        (field (name "MANUFACTURER") "Yageo")
        (field (name "MANUFACTURER PART NUMBER") "RC0805FR-07560RL")
      )
      (libsource (lib "Pin28_Schematic_Library") (part "RC0805FR-07560RL"))
    )
    (comp (ref "R13")
      (value "RC0805FR-0710KL")
      (footprint "R0805 1K")
      (description "RES SMD 10K OHM 1% 1/8W 0805")
      (fields
        (field (name "MANUFACTURER") "Yageo")
        (field (name "TOLERANCE") "1%")
        (field (name "RESISTANCE") "10kR")
      )
      (libsource (lib "Pin28_Schematic_Library") (part "RC0805FR-0710KL"))
    )
    (comp (ref "R14")
      (value "0R")
      (footprint "R0805 1K")
      (description "Surface Mount Thick Film Resistor, RC Series, 125 mW, - 5%, 150 V, 0805 [2012 Metric]")
      (fields
        (field (name "MANUFACTURER") "Yageo")
        (field (name "MANUFACTURER PART NUMBER") "RC0805JR-070RL")
      )
      (libsource (lib "Pin28_Schematic_Library") (part "RC0805JR-070RL"))
    )
    (comp (ref "R15")
      (value "0R")
      (footprint "R0805 1K")
      (description "Surface Mount Thick Film Resistor, RC Series, 125 mW, - 5%, 150 V, 0805 [2012 Metric]")
      (fields
        (field (name "MANUFACTURER") "Yageo")
        (field (name "MANUFACTURER PART NUMBER") "RC0805JR-070RL")
      )
      (libsource (lib "Pin28_Schematic_Library") (part "RC0805JR-070RL"))
    )
    (comp (ref "R16")
      (value "1M")
      (footprint "R0805 1M")
      (description "1M Ohm Res Thick Film 0805 1% 0.125W(1/8W) ±100ppm/C Epoxy SMD T/R")
      (fields (field (name "MANUFACTURER") "Yageo Phycomp") (field (name "TOLERANCE") "1%"))
      (libsource (lib "Pin28_Schematic_Library") (part "RC0805FR-071ML"))
    )
    (comp (ref "R17")
      (value "1K ohm")
      (footprint "R0805 1M")
      (fields
        (field (name "MANUFACTURER") "Yageo")
        (field (name "MANUFACTURER PART NUMBER") "RC0805FR-071KL")
        (field (name "TOLERANCE") "1%")
      )
      (libsource (lib "Pin28_Schematic_Library") (part "RC0805FR-071KL"))
    )
    (comp (ref "R18")
      (value "1K ohm")
      (footprint "R0805 1M")
      (fields
        (field (name "MANUFACTURER") "Yageo")
        (field (name "MANUFACTURER PART NUMBER") "RC0805FR-071KL")
        (field (name "TOLERANCE") "1%")
      )
      (libsource (lib "Pin28_Schematic_Library") (part "RC0805FR-071KL"))
    )
    (comp (ref "R19")
      (value "RC0805FR-0710KL")
      (footprint "R0805 1K")
      (description "RES SMD 10K OHM 1% 1/8W 0805")
      (fields
        (field (name "MANUFACTURER") "Yageo")
        (field (name "TOLERANCE") "1%")
        (field (name "RESISTANCE") "10kR")
      )
      (libsource (lib "Pin28_Schematic_Library") (part "RC0805FR-0710KL"))
    )
    (comp (ref "R20")
      (value "RC0805FR-0710KL")
      (footprint "R0805 1K")
      (description "RES SMD 10K OHM 1% 1/8W 0805")
      (fields
        (field (name "MANUFACTURER") "Yageo")
        (field (name "TOLERANCE") "1%")
        (field (name "RESISTANCE") "10kR")
      )
      (libsource (lib "Pin28_Schematic_Library") (part "RC0805FR-0710KL"))
    )
    (comp (ref "R21")
      (value "RC0805FR-0710KL")
      (footprint "R0805 1K")
      (description "RES SMD 10K OHM 1% 1/8W 0805")
      (fields
        (field (name "MANUFACTURER") "Yageo")
        (field (name "TOLERANCE") "1%")
        (field (name "RESISTANCE") "10kR")
      )
      (libsource (lib "Pin28_Schematic_Library") (part "RC0805FR-0710KL"))
    )
    (comp (ref "R22")
      (value "560 ohm")
      (footprint "R0805 1K")
      (description "Surface Mount Thick Film Resistor, RC Series, 560 ohm, 125 mW, - 1%, 150 V, 0805 [2012 Metric]")
      (fields
        (field (name "MANUFACTURER") "Yageo")
        (field (name "MANUFACTURER PART NUMBER") "RC0805FR-07560RL")
      )
      (libsource (lib "Pin28_Schematic_Library") (part "RC0805FR-07560RL"))
    )
    (comp (ref "R23")
      (value "22 R")
      (footprint "R0805 1K")
      (description "RES SMD 22 OHM 1% 1/8W 0805")
      (fields
        (field (name "MANUFACTURER") "Yageo")
        (field (name "MANUFACTURER PART NUMBER") "AC0805FR-0722RL")
      )
      (libsource (lib "Pin28_Schematic_Library") (part "AC0805FR-0722RL"))
    )
    (comp (ref "SCKT FOR U1")
      (value "28-DIP Socket")
      (footprint "28-DIP, 7.6mm Socket")
      (description "CONN IC DIP SOCKET 28POS TIN")
      (fields (field (name "MANUFACTURER") "3M") (field (name "MANUFACTURER PART NUMBER") "4828-3004-CP"))
      (libsource (lib "Pin28_Schematic_Library") (part "4828-3004-CP"))
    )
    (comp (ref "SW1")
      (value "450-1650-ND")
      (footprint "1825910-6")
      (description "SWITCH TACTILE SPST-NO 0.05A 24V")
      (fields
        (field (name "MANUFACTURER") "TE Connectivity Alcoswitch")
        (field (name "MANUFACTURER PART NUMBER") "1825910-6")
      )
      (libsource (lib "Pin28_Schematic_Library") (part "1825910-6"))
    )
    (comp (ref "SW2")
      (value "450-1650-ND")
      (footprint "1825910-6")
      (description "SWITCH TACTILE SPST-NO 0.05A 24V")
      (fields
        (field (name "MANUFACTURER") "TE Connectivity Alcoswitch")
        (field (name "MANUFACTURER PART NUMBER") "1825910-6")
      )
      (libsource (lib "Pin28_Schematic_Library") (part "1825910-6"))
    )
    (comp (ref "U1")
      (value "ATMEGA328P-PU")
      (footprint "DIP28")
      (description "ATMEGA328P-PU; 8 bit Microcontroller AVR 20MHz 1; 32kb Flash; 2kb RAM; I2C SPI 2")
      (fields (field (name "MANUFACTURER") "Microchip / Atmel"))
      (libsource (lib "Pin28_Schematic_Library") (part "ATMEGA328P-PU"))
    )
    (comp (ref "U2")
      (value "ATMEGA16U2-AU")
      (footprint "TQFP32")
      (description "MICROCHIP - ATMEGA16U2-AU - MCU, 8BIT, MEGAAVR, 16MHZ, TQFP-32")
      (fields (field (name "MANUFACTURER") "Microchip / Atmel"))
      (libsource (lib "Pin28_Schematic_Library") (part "ATMEGA16U2-AU"))
    )
    (comp (ref "U3")
      (value "SN74AHC1G09DBVR")
      (footprint "DBV_SOT_23_5")
      (description "TEXAS INSTRUMENTS - SN74AHC1G09DBVR - AND Gate, 74AHC1G09, 2 Input, 2 V to 5.5 V, SOT-23-5")
      (fields (field (name "MANUFACTURER") "Texas Instruments"))
      (libsource (lib "") (part "SN74AHC1G09DBVR_1"))
    )
    (comp (ref "U4")
      (value "TL1963A-33DCQR")
      (footprint "DCQ (R-PDSO-G6)")
      (description "IC REG LINEAR 3.3V 1.5A SOT223-6")
      (fields (field (name "MANUFACTURER") "Texas Instruments"))
      (libsource (lib "Pin28_Schematic_Library") (part "TL1963A-33DCQR"))
    )
    (comp (ref "U5")
      (value "SN74AHC1G09DBVR")
      (footprint "DBV_SOT_23_5")
      (description "TEXAS INSTRUMENTS - SN74AHC1G09DBVR - AND Gate, 74AHC1G09, 2 Input, 2 V to 5.5 V, SOT-23-5")
      (fields (field (name "MANUFACTURER") "Texas Instruments"))
      (libsource (lib "Pin28_Schematic_Library") (part "SN74AHC1G09DBVR"))
    )
    (comp (ref "U6")
      (value "SN74AHC1G09DBVR")
      (footprint "DBV_SOT_23_5")
      (description "TEXAS INSTRUMENTS - SN74AHC1G09DBVR - AND Gate, 74AHC1G09, 2 Input, 2 V to 5.5 V, SOT-23-5")
      (fields (field (name "MANUFACTURER") "Texas Instruments"))
      (libsource (lib "Pin28_Schematic_Library") (part "SN74AHC1G09DBVR"))
    )
    (comp (ref "U7")
      (value "SN74AHC1G09DBVR")
      (footprint "DBV_SOT_23_5")
      (description "TEXAS INSTRUMENTS - SN74AHC1G09DBVR - AND Gate, 74AHC1G09, 2 Input, 2 V to 5.5 V, SOT-23-5")
      (fields (field (name "MANUFACTURER") "Texas Instruments"))
      (libsource (lib "Pin28_Schematic_Library") (part "SN74AHC1G09DBVR"))
    )
    (comp (ref "Y1")
      (value "M7-16.000MHZ-D2Y-T")
      (footprint "Crystal 16Mhz")
      (description "CRYSTAL 16 MHZ 18PF SMD")
      (fields (field (name "MANUFACTURER") "Abracon") (field (name "TOLERANCE") "20ppm"))
      (libsource (lib "Pin28_Schematic_Library") (part "ABM7-16.000MHZ-D2Y-T"))
    )
    (comp (ref "Y2")
      (value "M7-16.000MHZ-D2Y-T")
      (footprint "Crystal 16Mhz")
      (description "CRYSTAL 16 MHZ 18PF SMD")
      (fields (field (name "MANUFACTURER") "Abracon") (field (name "TOLERANCE") "20ppm"))
      (libsource (lib "Pin28_Schematic_Library") (part "ABM7-16.000MHZ-D2Y-T"))
    )
    (comp (ref "Z1")
      (value "CG0603MLC-05E")
      (footprint "R0603")
      (description "VARISTOR 0603")
      (fields (field (name "MANUFACTURER") "Bourns") (field (name "VOLTAGE") "5V"))
      (libsource (lib "Pin28_Schematic_Library") (part "CG0603MLC-05E"))
    )
    (comp (ref "Z2")
      (value "CG0603MLC-05E")
      (footprint "R0603")
      (description "VARISTOR 0603")
      (fields (field (name "MANUFACTURER") "Bourns") (field (name "VOLTAGE") "5V"))
      (libsource (lib "Pin28_Schematic_Library") (part "CG0603MLC-05E"))
    )
  )
  (nets
    (net (code "1") (name "+3V3") (class "Default")
      (node (ref "C18") (pin "2") (pinfunction "2_2") (pintype "passive"))
      (node (ref "C25") (pin "2") (pinfunction "2_2") (pintype "passive"))
      (node (ref "J1") (pin "4") (pinfunction "4_4") (pintype "passive"))
      (node (ref "JP4") (pin "3") (pinfunction "3_3") (pintype "passive"))
      (node (ref "R15") (pin "2") (pinfunction "2_2") (pintype "passive"))
      (node (ref "U4") (pin "4") (pinfunction "OUT_4") (pintype "passive"))
      (node (ref "U4") (pin "5") (pinfunction "SENSE_5") (pintype "passive"))
    )
    (net (code "2") (name "+5V") (class "Default")
      (node (ref "C15") (pin "2") (pinfunction "2_2") (pintype "passive"))
      (node (ref "C16") (pin "2") (pinfunction "2_2") (pintype "passive"))
      (node (ref "C24") (pin "2") (pinfunction "2_2") (pintype "passive"))
      (node (ref "C3") (pin "1") (pinfunction "1_1") (pintype "passive"))
      (node (ref "J1") (pin "5") (pinfunction "5_5") (pintype "passive"))
      (node (ref "J27") (pin "1") (pinfunction "1_1") (pintype "passive"))
      (node (ref "JP4") (pin "1") (pinfunction "1_1") (pintype "passive"))
      (node (ref "L1") (pin "1") (pinfunction "1_1") (pintype "passive"))
      (node (ref "R14") (pin "1") (pinfunction "1_1") (pintype "passive"))
      (node (ref "U2") (pin "31") (pinfunction "UVCC_31") (pintype "passive"))
      (node (ref "U4") (pin "1") (pinfunction "~{SHDN}_1") (pintype "passive"))
      (node (ref "U4") (pin "2") (pinfunction "IN_2") (pintype "passive"))
    )
    (net (code "3") (name "+5V{slash}3V3") (class "Default")
      (node (ref "C17") (pin "2") (pinfunction "2_2") (pintype "passive"))
      (node (ref "C19") (pin "2") (pinfunction "2_2") (pintype "passive"))
      (node (ref "C20") (pin "2") (pinfunction "2_2") (pintype "passive"))
      (node (ref "C29") (pin "2") (pinfunction "2_2") (pintype "passive"))
      (node (ref "C30") (pin "2") (pinfunction "2_2") (pintype "passive"))
      (node (ref "C33") (pin "2") (pinfunction "2_2") (pintype "passive"))
      (node (ref "C8") (pin "2") (pinfunction "2_2") (pintype "passive"))
      (node (ref "D1") (pin "1") (pinfunction "cathod_1") (pintype "passive"))
      (node (ref "D6") (pin "1") (pinfunction "cathod_1") (pintype "passive"))
      (node (ref "FB1") (pin "1") (pinfunction "1_1") (pintype "passive"))
      (node (ref "FB2") (pin "1") (pinfunction "1_1") (pintype "passive"))
      (node (ref "FB3") (pin "1") (pinfunction "1_1") (pintype "passive"))
      (node (ref "J1") (pin "2") (pinfunction "2_2") (pintype "passive"))
      (node (ref "J5") (pin "2") (pinfunction "2_2") (pintype "passive"))
      (node (ref "R1") (pin "2") (pinfunction "2_2") (pintype "passive"))
      (node (ref "R12") (pin "2") (pinfunction "2_2") (pintype "passive"))
      (node (ref "R13") (pin "2") (pinfunction "2_2") (pintype "passive"))
      (node (ref "R19") (pin "1") (pinfunction "1_1") (pintype "passive"))
      (node (ref "R2") (pin "2") (pinfunction "2_2") (pintype "passive"))
      (node (ref "R20") (pin "2") (pinfunction "2_2") (pintype "passive"))
      (node (ref "R21") (pin "1") (pinfunction "1_1") (pintype "passive"))
      (node (ref "R3") (pin "1") (pinfunction "1_1") (pintype "passive"))
      (node (ref "R5") (pin "2") (pinfunction "2_2") (pintype "passive"))
      (node (ref "R6") (pin "2") (pinfunction "2_2") (pintype "passive"))
      (node (ref "R7") (pin "1") (pinfunction "1_1") (pintype "passive"))
      (node (ref "U3") (pin "5") (pinfunction "5_5") (pintype "passive"))
      (node (ref "U5") (pin "5") (pinfunction "5_5") (pintype "passive"))
      (node (ref "U6") (pin "5") (pinfunction "5_5") (pintype "passive"))
      (node (ref "U7") (pin "5") (pinfunction "5_5") (pintype "passive"))
    )
    (net (code "4") (name "+5{slash}3V3") (class "Default")
      (node (ref "JP4") (pin "2") (pinfunction "2_2") (pintype "passive"))
      (node (ref "R14") (pin "2") (pinfunction "2_2") (pintype "passive"))
      (node (ref "R15") (pin "1") (pinfunction "1_1") (pintype "passive"))
    )
    (net (code "5") (name "+AREF") (class "Default")
      (node (ref "C21") (pin "2") (pinfunction "2_2") (pintype "passive"))
      (node (ref "C28") (pin "2") (pinfunction "2_2") (pintype "passive"))
      (node (ref "J4") (pin "8") (pinfunction "8_8") (pintype "passive"))
      (node (ref "U1") (pin "21") (pinfunction "AREF_21") (pintype "passive"))
    )
    (net (code "6") (name "/16U HDR RESETn") (class "Default")
      (node (ref "J6") (pin "5") (pinfunction "5_5") (pintype "passive"))
      (node (ref "JP3") (pin "3") (pinfunction "3_3") (pintype "passive"))
    )
    (net (code "7") (name "/16U RESETn") (class "Default")
      (node (ref "JP3") (pin "4") (pinfunction "4_4") (pintype "passive"))
      (node (ref "R20") (pin "1") (pinfunction "1_1") (pintype "passive"))
      (node (ref "U2") (pin "24") (pinfunction "~{Reset}_(PC1_/_dW)_24") (pintype "passive"))
      (node (ref "U7") (pin "4") (pinfunction "10_4") (pintype "passive"))
    )
    (net (code "8") (name "/16U2PROG 328P RESETn") (class "Default")
      (node (ref "JP1") (pin "2") (pinfunction "2_2") (pintype "passive"))
      (node (ref "R7") (pin "2") (pinfunction "2_2") (pintype "passive"))
      (node (ref "U2") (pin "13") (pinfunction "~{HWB}_/_AIN6_/_T0_/_INT7)_PD7_13") (pintype "passive"))
    )
    (net (code "9") (name "/328P AUTORESETn") (class "Default")
      (node (ref "C11") (pin "2") (pinfunction "2_2") (pintype "passive"))
      (node (ref "R1") (pin "1") (pinfunction "1_1") (pintype "passive"))
      (node (ref "U5") (pin "1") (pinfunction "1_1") (pintype "passive"))
    )
    (net (code "10") (name "/328P BUF RESETn") (class "Default")
      (node (ref "C10") (pin "2") (pinfunction "2_2") (pintype "passive"))
      (node (ref "C31") (pin "2") (pinfunction "2_2") (pintype "passive"))
      (node (ref "D1") (pin "2") (pinfunction "anode_2") (pintype "passive"))
      (node (ref "D6") (pin "2") (pinfunction "anode_2") (pintype "passive"))
      (node (ref "R19") (pin "2") (pinfunction "2_2") (pintype "passive"))
      (node (ref "R3") (pin "2") (pinfunction "2_2") (pintype "passive"))
      (node (ref "SW1") (pin "3") (pinfunction "3_3") (pintype "passive"))
      (node (ref "SW1") (pin "4") (pinfunction "4_4") (pintype "passive"))
      (node (ref "U5") (pin "2") (pinfunction "2_2") (pintype "passive"))
      (node (ref "U7") (pin "1") (pinfunction "1_1") (pintype "passive"))
      (node (ref "U7") (pin "2") (pinfunction "2_2") (pintype "passive"))
    )
    (net (code "11") (name "/328P RESETn") (class "Default")
      (node (ref "J1") (pin "3") (pinfunction "3_3") (pintype "passive"))
      (node (ref "J5") (pin "5") (pinfunction "5_5") (pintype "passive"))
      (node (ref "JP3") (pin "1") (pinfunction "1_1") (pintype "passive"))
      (node (ref "R13") (pin "1") (pinfunction "1_1") (pintype "passive"))
      (node (ref "U1") (pin "1") (pinfunction "(PCINT14/~{RESET})_PC6_1") (pintype "passive"))
      (node (ref "U5") (pin "4") (pinfunction "10_4") (pintype "passive"))
    )
    (net (code "12") (name "/CON USB N") (class "Default")
      (node (ref "R9") (pin "1") (pinfunction "1_1") (pintype "passive"))
      (node (ref "Z2") (pin "2") (pinfunction "2_2") (pintype "passive"))
      (node (ref "j10") (pin "2") (pinfunction "2_2") (pintype "passive"))
    )
    (net (code "13") (name "/CON USB P") (class "Default")
      (node (ref "R11") (pin "1") (pinfunction "1_1") (pintype "passive"))
      (node (ref "Z1") (pin "2") (pinfunction "2_2") (pintype "passive"))
      (node (ref "j10") (pin "3") (pinfunction "3_3") (pintype "passive"))
    )
    (net (code "14") (name "/IO8") (class "Default")
      (node (ref "J4") (pin "1") (pinfunction "1_1") (pintype "passive"))
      (node (ref "R22") (pin "2") (pinfunction "2_2") (pintype "passive"))
      (node (ref "U1") (pin "14") (pinfunction "(PCINT0/CLKO/ICP1)_PB0_14") (pintype "passive"))
    )
    (net (code "15") (name "/PD0{slash}RX") (class "Default")
      (node (ref "R17") (pin "1") (pinfunction "1_1") (pintype "passive"))
      (node (ref "U2") (pin "9") (pinfunction "(TXD1_/_INT3)_PD3_9") (pintype "passive"))
    )
    (net (code "16") (name "/PD1{slash}TX") (class "Default")
      (node (ref "R18") (pin "1") (pinfunction "1_1") (pintype "passive"))
      (node (ref "U2") (pin "8") (pinfunction "(RXD1_/_AIN1_/_INT2)_PD2_8") (pintype "passive"))
    )
    (net (code "17") (name "/USB N") (class "Default")
      (node (ref "R9") (pin "2") (pinfunction "2_2") (pintype "passive"))
      (node (ref "U2") (pin "30") (pinfunction "D-_30") (pintype "passive"))
    )
    (net (code "18") (name "/USB P") (class "Default")
      (node (ref "R11") (pin "2") (pinfunction "2_2") (pintype "passive"))
      (node (ref "U2") (pin "29") (pinfunction "D+_29") (pintype "passive"))
    )
    (net (code "19") (name "/USER BUTTON") (class "Default")
      (node (ref "R21") (pin "2") (pinfunction "2_2") (pintype "passive"))
      (node (ref "R23") (pin "1") (pinfunction "1_1") (pintype "passive"))
      (node (ref "SW2") (pin "3") (pinfunction "3_3") (pintype "passive"))
      (node (ref "SW2") (pin "4") (pinfunction "4_4") (pintype "passive"))
    )
    (net (code "20") (name "/USER BUTTON BUF") (class "Default")
      (node (ref "C32") (pin "2") (pinfunction "2_2") (pintype "passive"))
      (node (ref "R23") (pin "2") (pinfunction "2_2") (pintype "passive"))
      (node (ref "U6") (pin "1") (pinfunction "1_1") (pintype "passive"))
      (node (ref "U6") (pin "2") (pinfunction "2_2") (pintype "passive"))
    )
    (net (code "21") (name "GND") (class "Default")
      (node (ref "C1") (pin "1") (pinfunction "1_1") (pintype "passive"))
      (node (ref "C10") (pin "1") (pinfunction "1_1") (pintype "passive"))
      (node (ref "C12") (pin "1") (pinfunction "1_1") (pintype "passive"))
      (node (ref "C13") (pin "1") (pinfunction "1_1") (pintype "passive"))
      (node (ref "C14") (pin "1") (pinfunction "1_1") (pintype "passive"))
      (node (ref "C15") (pin "1") (pinfunction "1_1") (pintype "passive"))
      (node (ref "C16") (pin "1") (pinfunction "1_1") (pintype "passive"))
      (node (ref "C17") (pin "1") (pinfunction "1_1") (pintype "passive"))
      (node (ref "C18") (pin "1") (pinfunction "1_1") (pintype "passive"))
      (node (ref "C19") (pin "1") (pinfunction "1_1") (pintype "passive"))
      (node (ref "C2") (pin "1") (pinfunction "1_1") (pintype "passive"))
      (node (ref "C20") (pin "1") (pinfunction "1_1") (pintype "passive"))
      (node (ref "C21") (pin "1") (pinfunction "1_1") (pintype "passive"))
      (node (ref "C22") (pin "1") (pinfunction "1_1") (pintype "passive"))
      (node (ref "C23") (pin "1") (pinfunction "1_1") (pintype "passive"))
      (node (ref "C24") (pin "1") (pinfunction "1_1") (pintype "passive"))
      (node (ref "C25") (pin "1") (pinfunction "1_1") (pintype "passive"))
      (node (ref "C26") (pin "1") (pinfunction "1_1") (pintype "passive"))
      (node (ref "C27") (pin "1") (pinfunction "1_1") (pintype "passive"))
      (node (ref "C28") (pin "1") (pinfunction "1_1") (pintype "passive"))
      (node (ref "C29") (pin "1") (pinfunction "1_1") (pintype "passive"))
      (node (ref "C3") (pin "2") (pinfunction "2_2") (pintype "passive"))
      (node (ref "C30") (pin "1") (pinfunction "1_1") (pintype "passive"))
      (node (ref "C31") (pin "1") (pinfunction "1_1") (pintype "passive"))
      (node (ref "C32") (pin "1") (pinfunction "1_1") (pintype "passive"))
      (node (ref "C33") (pin "1") (pinfunction "1_1") (pintype "passive"))
      (node (ref "C4") (pin "2") (pinfunction "2_2") (pintype "passive"))
      (node (ref "C5") (pin "1") (pinfunction "1_1") (pintype "passive"))
      (node (ref "C6") (pin "1") (pinfunction "1_1") (pintype "passive"))
      (node (ref "C7") (pin "1") (pinfunction "1_1") (pintype "passive"))
      (node (ref "C8") (pin "1") (pinfunction "1_1") (pintype "passive"))
      (node (ref "C9") (pin "1") (pinfunction "1_1") (pintype "passive"))
      (node (ref "D2") (pin "1") (pinfunction "cathod_1") (pintype "passive"))
      (node (ref "J1") (pin "6") (pinfunction "6_6") (pintype "passive"))
      (node (ref "J1") (pin "7") (pinfunction "7_7") (pintype "passive"))
      (node (ref "J29") (pin "1") (pinfunction "1_1") (pintype "passive"))
      (node (ref "J4") (pin "7") (pinfunction "7_7") (pintype "passive"))
      (node (ref "J5") (pin "6") (pinfunction "6_6") (pintype "passive"))
      (node (ref "J6") (pin "6") (pinfunction "6_6") (pintype "passive"))
      (node (ref "MH1") (pin "1") (pinfunction "1_1") (pintype "passive"))
      (node (ref "MH2") (pin "1") (pinfunction "1_1") (pintype "passive"))
      (node (ref "MH3") (pin "1") (pinfunction "1_1") (pintype "passive"))
      (node (ref "R10") (pin "2") (pinfunction "2_2") (pintype "passive"))
      (node (ref "R8") (pin "1") (pinfunction "1_1") (pintype "passive"))
      (node (ref "SW1") (pin "1") (pinfunction "1_1") (pintype "passive"))
      (node (ref "SW1") (pin "2") (pinfunction "2_2") (pintype "passive"))
      (node (ref "SW2") (pin "1") (pinfunction "1_1") (pintype "passive"))
      (node (ref "SW2") (pin "2") (pinfunction "2_2") (pintype "passive"))
      (node (ref "U1") (pin "22") (pinfunction "GND_22") (pintype "passive"))
      (node (ref "U1") (pin "8") (pinfunction "GND_8") (pintype "passive"))
      (node (ref "U2") (pin "28") (pinfunction "UGND_28") (pintype "passive"))
      (node (ref "U2") (pin "3") (pinfunction "GND_3") (pintype "passive"))
      (node (ref "U3") (pin "3") (pinfunction "3_3") (pintype "passive"))
      (node (ref "U4") (pin "3") (pinfunction "GND_3") (pintype "passive"))
      (node (ref "U4") (pin "6") (pinfunction "EPAD_6") (pintype "passive"))
      (node (ref "U5") (pin "3") (pinfunction "3_3") (pintype "passive"))
      (node (ref "U6") (pin "3") (pinfunction "3_3") (pintype "passive"))
      (node (ref "U7") (pin "3") (pinfunction "3_3") (pintype "passive"))
      (node (ref "Z1") (pin "1") (pinfunction "1_1") (pintype "passive"))
      (node (ref "Z2") (pin "1") (pinfunction "1_1") (pintype "passive"))
      (node (ref "j10") (pin "10") (pinfunction "10_10") (pintype "passive"))
      (node (ref "j10") (pin "11") (pinfunction "11_11") (pintype "passive"))
      (node (ref "j10") (pin "5") (pinfunction "5_5") (pintype "passive"))
      (node (ref "j10") (pin "6") (pinfunction "6_6") (pintype "passive"))
      (node (ref "j10") (pin "7") (pinfunction "7_7") (pintype "passive"))
      (node (ref "j10") (pin "8") (pinfunction "8_8") (pintype "passive"))
      (node (ref "j10") (pin "9") (pinfunction "9_9") (pintype "passive"))
    )
    (net (code "22") (name "Net-(C11-Pad1)") (class "Default")
      (node (ref "C11") (pin "1") (pinfunction "1_1") (pintype "passive"))
      (node (ref "JP1") (pin "1") (pinfunction "1_1") (pintype "passive"))
    )
    (net (code "23") (name "Net-(D2-anode)") (class "Default")
      (node (ref "D2") (pin "2") (pinfunction "anode_2") (pintype "passive"))
      (node (ref "R2") (pin "1") (pinfunction "1_1") (pintype "passive"))
    )
    (net (code "24") (name "Net-(D3-anode)") (class "Default")
      (node (ref "D3") (pin "2") (pinfunction "anode_2") (pintype "passive"))
      (node (ref "R5") (pin "1") (pinfunction "1_1") (pintype "passive"))
    )
    (net (code "25") (name "Net-(D3-cathod)") (class "Default")
      (node (ref "D3") (pin "1") (pinfunction "cathod_1") (pintype "passive"))
      (node (ref "U2") (pin "11") (pinfunction "XCK_AIN4_/_PCINT12)_PD5_11") (pintype "passive"))
    )
    (net (code "26") (name "Net-(D4-anode)") (class "Default")
      (node (ref "D4") (pin "2") (pinfunction "anode_2") (pintype "passive"))
      (node (ref "R6") (pin "1") (pinfunction "1_1") (pintype "passive"))
    )
    (net (code "27") (name "Net-(D4-cathod)") (class "Default")
      (node (ref "D4") (pin "1") (pinfunction "cathod_1") (pintype "passive"))
      (node (ref "U2") (pin "10") (pinfunction "INT5/_AIN3)_PD4_10") (pintype "passive"))
    )
    (net (code "28") (name "Net-(D5-anode)") (class "Default")
      (node (ref "D5") (pin "2") (pinfunction "anode_2") (pintype "passive"))
      (node (ref "R12") (pin "1") (pinfunction "1_1") (pintype "passive"))
    )
    (net (code "29") (name "Net-(D5-cathod)") (class "Default")
      (node (ref "D5") (pin "1") (pinfunction "cathod_1") (pintype "passive"))
      (node (ref "U3") (pin "4") (pinfunction "10_4") (pintype "passive"))
    )
    (net (code "30") (name "Net-(JP1-Pad3)") (class "Default")
      (node (ref "JP1") (pin "3") (pinfunction "3_3") (pintype "passive"))
      (node (ref "R8") (pin "2") (pinfunction "2_2") (pintype "passive"))
    )
    (net (code "31") (name "Net-(L1-10)") (class "Default")
      (node (ref "C4") (pin "1") (pinfunction "1_1") (pintype "passive"))
      (node (ref "L1") (pin "2") (pinfunction "10_2") (pintype "passive"))
      (node (ref "j10") (pin "1") (pinfunction "1_1") (pintype "passive"))
    )
    (net (code "32") (name "Net-(R10-Pad1)") (class "Default")
      (node (ref "R10") (pin "1") (pinfunction "1_1") (pintype "passive"))
      (node (ref "j10") (pin "4") (pinfunction "4_4") (pintype "passive"))
    )
    (net (code "33") (name "Net-(U1-(PCINT6{slash}XTAL1{slash}TOSC1)_PB6)") (class "Default")
      (node (ref "C7") (pin "2") (pinfunction "2_2") (pintype "passive"))
      (node (ref "R16") (pin "1") (pinfunction "1_1") (pintype "passive"))
      (node (ref "U1") (pin "9") (pinfunction "(PCINT6/XTAL1/TOSC1)_PB6_9") (pintype "passive"))
      (node (ref "Y2") (pin "1") (pinfunction "1_1") (pintype "passive"))
    )
    (net (code "34") (name "Net-(U1-(PCINT7{slash}XTAL2{slash}TOSC2)_PB7)") (class "Default")
      (node (ref "C6") (pin "2") (pinfunction "2_2") (pintype "passive"))
      (node (ref "R16") (pin "2") (pinfunction "2_2") (pintype "passive"))
      (node (ref "U1") (pin "10") (pinfunction "(PCINT7/XTAL2/TOSC2)_PB7_10") (pintype "passive"))
      (node (ref "Y2") (pin "2") (pinfunction "2_2") (pintype "passive"))
    )
    (net (code "35") (name "Net-(U1-(PCINT16{slash}RXD)_PD0)") (class "Default")
      (node (ref "J3") (pin "1") (pinfunction "1_1") (pintype "passive"))
      (node (ref "R17") (pin "2") (pinfunction "2_2") (pintype "passive"))
      (node (ref "U1") (pin "2") (pinfunction "(PCINT16/RXD)_PD0_2") (pintype "passive"))
    )
    (net (code "36") (name "Net-(U1-(PCINT17{slash}TXD)_PD1)") (class "Default")
      (node (ref "J3") (pin "2") (pinfunction "2_2") (pintype "passive"))
      (node (ref "R18") (pin "2") (pinfunction "2_2") (pintype "passive"))
      (node (ref "U1") (pin "3") (pinfunction "(PCINT17/TXD)_PD1_3") (pintype "passive"))
    )
    (net (code "37") (name "Net-(U1-(PCINT18{slash}INT0)_PD2)") (class "Default")
      (node (ref "J3") (pin "3") (pinfunction "3_3") (pintype "passive"))
      (node (ref "U1") (pin "4") (pinfunction "(PCINT18/INT0)_PD2_4") (pintype "passive"))
    )
    (net (code "38") (name "Net-(U1-(PCINT19{slash}OC2B{slash}INT1)_PD3)") (class "Default")
      (node (ref "J3") (pin "4") (pinfunction "4_4") (pintype "passive"))
      (node (ref "U1") (pin "5") (pinfunction "(PCINT19/OC2B/INT1)_PD3_5") (pintype "passive"))
    )
    (net (code "39") (name "Net-(U1-(PCINT20{slash}XCK{slash}T0)_PD4)") (class "Default")
      (node (ref "J3") (pin "5") (pinfunction "5_5") (pintype "passive"))
      (node (ref "U1") (pin "6") (pinfunction "(PCINT20/XCK/T0)_PD4_6") (pintype "passive"))
    )
    (net (code "40") (name "Net-(U1-(PCINT21{slash}OC0B{slash}T1)_PD5)") (class "Default")
      (node (ref "J3") (pin "6") (pinfunction "6_6") (pintype "passive"))
      (node (ref "U1") (pin "11") (pinfunction "(PCINT21/OC0B/T1)_PD5_11") (pintype "passive"))
    )
    (net (code "41") (name "Net-(U1-(PCINT22{slash}OC0A{slash}AIN0)_PD6)") (class "Default")
      (node (ref "J3") (pin "7") (pinfunction "7_7") (pintype "passive"))
      (node (ref "U1") (pin "12") (pinfunction "(PCINT22/OC0A/AIN0)_PD6_12") (pintype "passive"))
    )
    (net (code "42") (name "Net-(U1-(PCINT23{slash}AIN1)_PD7)") (class "Default")
      (node (ref "J3") (pin "8") (pinfunction "8_8") (pintype "passive"))
      (node (ref "U1") (pin "13") (pinfunction "(PCINT23/AIN1)_PD7_13") (pintype "passive"))
    )
    (net (code "43") (name "Net-(U1-AVCC)") (class "Default")
      (node (ref "C26") (pin "2") (pinfunction "2_2") (pintype "passive"))
      (node (ref "C27") (pin "2") (pinfunction "2_2") (pintype "passive"))
      (node (ref "FB3") (pin "2") (pinfunction "2_2") (pintype "passive"))
      (node (ref "U1") (pin "20") (pinfunction "AVCC_20") (pintype "passive"))
    )
    (net (code "44") (name "Net-(U1-PB1_(OC1A{slash}PCINT1))") (class "Default")
      (node (ref "J4") (pin "2") (pinfunction "2_2") (pintype "passive"))
      (node (ref "U1") (pin "15") (pinfunction "PB1_(OC1A/PCINT1)_15") (pintype "passive"))
    )
    (net (code "45") (name "Net-(U1-PB2_(SS{slash}OC1B{slash}PCINT2))") (class "Default")
      (node (ref "J4") (pin "3") (pinfunction "3_3") (pintype "passive"))
      (node (ref "U1") (pin "16") (pinfunction "PB2_(SS/OC1B/PCINT2)_16") (pintype "passive"))
    )
    (net (code "46") (name "Net-(U1-PB3_(MOSI{slash}OC2A{slash}PCINT3))") (class "Default")
      (node (ref "J4") (pin "4") (pinfunction "4_4") (pintype "passive"))
      (node (ref "J5") (pin "4") (pinfunction "4_4") (pintype "passive"))
      (node (ref "U1") (pin "17") (pinfunction "PB3_(MOSI/OC2A/PCINT3)_17") (pintype "passive"))
    )
    (net (code "47") (name "Net-(U1-PB4_(MISO{slash}PCINT4))") (class "Default")
      (node (ref "J4") (pin "5") (pinfunction "5_5") (pintype "passive"))
      (node (ref "J5") (pin "1") (pinfunction "1_1") (pintype "passive"))
      (node (ref "U1") (pin "18") (pinfunction "PB4_(MISO/PCINT4)_18") (pintype "passive"))
    )
    (net (code "48") (name "Net-(U1-PB5_(SCK{slash}PCINT5))") (class "Default")
      (node (ref "J4") (pin "6") (pinfunction "6_6") (pintype "passive"))
      (node (ref "J5") (pin "3") (pinfunction "3_3") (pintype "passive"))
      (node (ref "U1") (pin "19") (pinfunction "PB5_(SCK/PCINT5)_19") (pintype "passive"))
      (node (ref "U3") (pin "1") (pinfunction "1_1") (pintype "passive"))
      (node (ref "U3") (pin "2") (pinfunction "2_2") (pintype "passive"))
    )
    (net (code "49") (name "Net-(U1-PC0_(ADC0{slash}PCINT8))") (class "Default")
      (node (ref "J2") (pin "1") (pinfunction "1_1") (pintype "passive"))
      (node (ref "U1") (pin "23") (pinfunction "PC0_(ADC0/PCINT8)_23") (pintype "passive"))
    )
    (net (code "50") (name "Net-(U1-PC1_(ADC1{slash}PCINT9))") (class "Default")
      (node (ref "J2") (pin "2") (pinfunction "2_2") (pintype "passive"))
      (node (ref "U1") (pin "24") (pinfunction "PC1_(ADC1/PCINT9)_24") (pintype "passive"))
    )
    (net (code "51") (name "Net-(U1-PC2_(ADC2{slash}PCINT10))") (class "Default")
      (node (ref "J2") (pin "3") (pinfunction "3_3") (pintype "passive"))
      (node (ref "U1") (pin "25") (pinfunction "PC2_(ADC2/PCINT10)_25") (pintype "passive"))
    )
    (net (code "52") (name "Net-(U1-PC3_(ADC3{slash}PCINT11))") (class "Default")
      (node (ref "J2") (pin "4") (pinfunction "4_4") (pintype "passive"))
      (node (ref "U1") (pin "26") (pinfunction "PC3_(ADC3/PCINT11)_26") (pintype "passive"))
    )
    (net (code "53") (name "Net-(U1-PC4_(ADC4{slash}SDA{slash}PCINT12))") (class "Default")
      (node (ref "J2") (pin "5") (pinfunction "5_5") (pintype "passive"))
      (node (ref "J4") (pin "9") (pinfunction "9_9") (pintype "passive"))
      (node (ref "U1") (pin "27") (pinfunction "PC4_(ADC4/SDA/PCINT12)_27") (pintype "passive"))
    )
    (net (code "54") (name "Net-(U1-PC5_(ADC5{slash}SCL{slash}PCINT13))") (class "Default")
      (node (ref "J2") (pin "6") (pinfunction "6_6") (pintype "passive"))
      (node (ref "J4") (pin "10") (pinfunction "10_10") (pintype "passive"))
      (node (ref "U1") (pin "28") (pinfunction "PC5_(ADC5/SCL/PCINT13)_28") (pintype "passive"))
    )
    (net (code "55") (name "Net-(U1-VCC)") (class "Default")
      (node (ref "C22") (pin "2") (pinfunction "2_2") (pintype "passive"))
      (node (ref "C23") (pin "2") (pinfunction "2_2") (pintype "passive"))
      (node (ref "FB2") (pin "2") (pinfunction "2_2") (pintype "passive"))
      (node (ref "U1") (pin "7") (pinfunction "VCC_7") (pintype "passive"))
    )
    (net (code "56") (name "Net-(U2-(PC0)_XTAL2)") (class "Default")
      (node (ref "C1") (pin "2") (pinfunction "2_2") (pintype "passive"))
      (node (ref "R4") (pin "2") (pinfunction "2_2") (pintype "passive"))
      (node (ref "U2") (pin "2") (pinfunction "(PC0)_XTAL2_2") (pintype "passive"))
      (node (ref "Y1") (pin "2") (pinfunction "2_2") (pintype "passive"))
    )
    (net (code "57") (name "Net-(U2-(PDI_{slash}_MOSI_{slash}_PCINT2)_PB2)") (class "Default")
      (node (ref "J6") (pin "4") (pinfunction "4_4") (pintype "passive"))
      (node (ref "U2") (pin "16") (pinfunction "(PDI_/_MOSI_/_PCINT2)_PB2_16") (pintype "passive"))
    )
    (net (code "58") (name "Net-(U2-(SCLK_{slash}_PCINT1)_PB1)") (class "Default")
      (node (ref "J6") (pin "3") (pinfunction "3_3") (pintype "passive"))
      (node (ref "U2") (pin "15") (pinfunction "(SCLK_/_PCINT1)_PB1_15") (pintype "passive"))
    )
    (net (code "59") (name "Net-(U2-AVCC)") (class "Default")
      (node (ref "C12") (pin "2") (pinfunction "2_2") (pintype "passive"))
      (node (ref "C13") (pin "2") (pinfunction "2_2") (pintype "passive"))
      (node (ref "C14") (pin "2") (pinfunction "2_2") (pintype "passive"))
      (node (ref "FB1") (pin "2") (pinfunction "2_2") (pintype "passive"))
      (node (ref "U2") (pin "32") (pinfunction "AVCC_32") (pintype "passive"))
      (node (ref "U2") (pin "4") (pinfunction "VCC_4") (pintype "passive"))
    )
    (net (code "60") (name "Net-(U2-PB3_(PDO_{slash}_MISO_{slash}_PCINT3))") (class "Default")
      (node (ref "J6") (pin "1") (pinfunction "1_1") (pintype "passive"))
      (node (ref "U2") (pin "17") (pinfunction "PB3_(PDO_/_MISO_/_PCINT3)_17") (pintype "passive"))
    )
    (net (code "61") (name "Net-(U2-PB4_(T1_{slash}_PCINT4))") (class "Default")
      (node (ref "JP2") (pin "1") (pinfunction "1_1") (pintype "passive"))
      (node (ref "JP3") (pin "2") (pinfunction "2_2") (pintype "passive"))
      (node (ref "U2") (pin "18") (pinfunction "PB4_(T1_/_PCINT4)_18") (pintype "passive"))
    )
    (net (code "62") (name "Net-(U2-PB5_(PCINT5))") (class "Default")
      (node (ref "JP2") (pin "3") (pinfunction "3_3") (pintype "passive"))
      (node (ref "U2") (pin "19") (pinfunction "PB5_(PCINT5)_19") (pintype "passive"))
    )
    (net (code "63") (name "Net-(U2-PB6_(PCINT6))") (class "Default")
      (node (ref "JP2") (pin "2") (pinfunction "2_2") (pintype "passive"))
      (node (ref "U2") (pin "20") (pinfunction "PB6_(PCINT6)_20") (pintype "passive"))
    )
    (net (code "64") (name "Net-(U2-PB7_(PCINT7_{slash}_OC.0A_{slash}_OC.1C))") (class "Default")
      (node (ref "JP2") (pin "4") (pinfunction "4_4") (pintype "passive"))
      (node (ref "U2") (pin "21") (pinfunction "PB7_(PCINT7_/_OC.0A_/_OC.1C)_21") (pintype "passive"))
    )
    (net (code "65") (name "Net-(U2-UCAP)") (class "Default")
      (node (ref "C5") (pin "2") (pinfunction "2_2") (pintype "passive"))
      (node (ref "U2") (pin "27") (pinfunction "UCAP_27") (pintype "passive"))
    )
    (net (code "66") (name "Net-(U2-XTAL1)") (class "Default")
      (node (ref "C2") (pin "2") (pinfunction "2_2") (pintype "passive"))
      (node (ref "R4") (pin "1") (pinfunction "1_1") (pintype "passive"))
      (node (ref "U2") (pin "1") (pinfunction "XTAL1_1") (pintype "passive"))
      (node (ref "Y1") (pin "1") (pinfunction "1_1") (pintype "passive"))
    )
    (net (code "67") (name "Net-(U6-10)") (class "Default")
      (node (ref "R22") (pin "1") (pinfunction "1_1") (pintype "passive"))
      (node (ref "U6") (pin "4") (pinfunction "10_4") (pintype "passive"))
    )
    (net (code "68") (name "VCC") (class "Default")
      (node (ref "C9") (pin "2") (pinfunction "2_2") (pintype "passive"))
      (node (ref "J6") (pin "2") (pinfunction "2_2") (pintype "passive"))
    )
    (net (code "69") (name "unconnected-(J1-Pad1)") (class "Default")
      (node (ref "J1") (pin "1") (pinfunction "1_1") (pintype "passive+no_connect"))
    )
    (net (code "70") (name "unconnected-(J1-Pad8)") (class "Default")
      (node (ref "J1") (pin "8") (pinfunction "8_8") (pintype "passive+no_connect"))
    )
    (net (code "71") (name "unconnected-(MH4-Pad1)") (class "Default")
      (node (ref "MH4") (pin "1") (pinfunction "1_1") (pintype "passive+no_connect"))
    )
    (net (code "72") (name "unconnected-(U2-(AIN0_{slash}_INT1)_PD1-Pad7)") (class "Default")
      (node (ref "U2") (pin "7") (pinfunction "(AIN0_/_INT1)_PD1_7") (pintype "passive+no_connect"))
    )
    (net (code "73") (name "unconnected-(U2-(OC.0B_{slash}_INT0)_PD0-Pad6)") (class "Default")
      (node (ref "U2") (pin "6") (pinfunction "(OC.0B_/_INT0)_PD0_6") (pintype "passive+no_connect"))
    )
    (net (code "74") (name "unconnected-(U2-(PCINT11_{slash}AIN2_)_PC2-Pad5)") (class "Default")
      (node (ref "U2") (pin "5") (pinfunction "(PCINT11_/AIN2_)_PC2_5") (pintype "passive+no_connect"))
    )
    (net (code "75") (name "unconnected-(U2-(~{RTS}_{slash}_AIN5_{slash}_INT6)_PD6-Pad12)") (class "Default")
      (node (ref "U2") (pin "12") (pinfunction "(~{RTS}_/_AIN5_/_INT6)_PD6_12") (pintype "passive+no_connect"))
    )
    (net (code "76") (name "unconnected-(U2-(~{SS}_{slash}_PCINT0)_PB0-Pad14)") (class "Default")
      (node (ref "U2") (pin "14") (pinfunction "(~{SS}_/_PCINT0)_PB0_14") (pintype "passive+no_connect"))
    )
    (net (code "77") (name "unconnected-(U2-PC4_(PCINT10)-Pad26)") (class "Default")
      (node (ref "U2") (pin "26") (pinfunction "PC4_(PCINT10)_26") (pintype "passive+no_connect"))
    )
    (net (code "78") (name "unconnected-(U2-PC5_(_PCINT9{slash}_OC.1B)-Pad25)") (class "Default")
      (node (ref "U2") (pin "25") (pinfunction "PC5_(_PCINT9/_OC.1B)_25") (pintype "passive+no_connect"))
    )
    (net (code "79") (name "unconnected-(U2-PC6_(OC.1A_{slash}_PCINT8)-Pad23)") (class "Default")
      (node (ref "U2") (pin "23") (pinfunction "PC6_(OC.1A_/_PCINT8)_23") (pintype "passive+no_connect"))
    )
    (net (code "80") (name "unconnected-(U2-PC7_(INT4_{slash}_ICP1_{slash}_CLKO)-Pad22)") (class "Default")
      (node (ref "U2") (pin "22") (pinfunction "PC7_(INT4_/_ICP1_/_CLKO)_22") (pintype "passive+no_connect"))
    )
  )
)
